# digital_input_module.net
KiCad netlist of a schematic drawn in Altium Designer
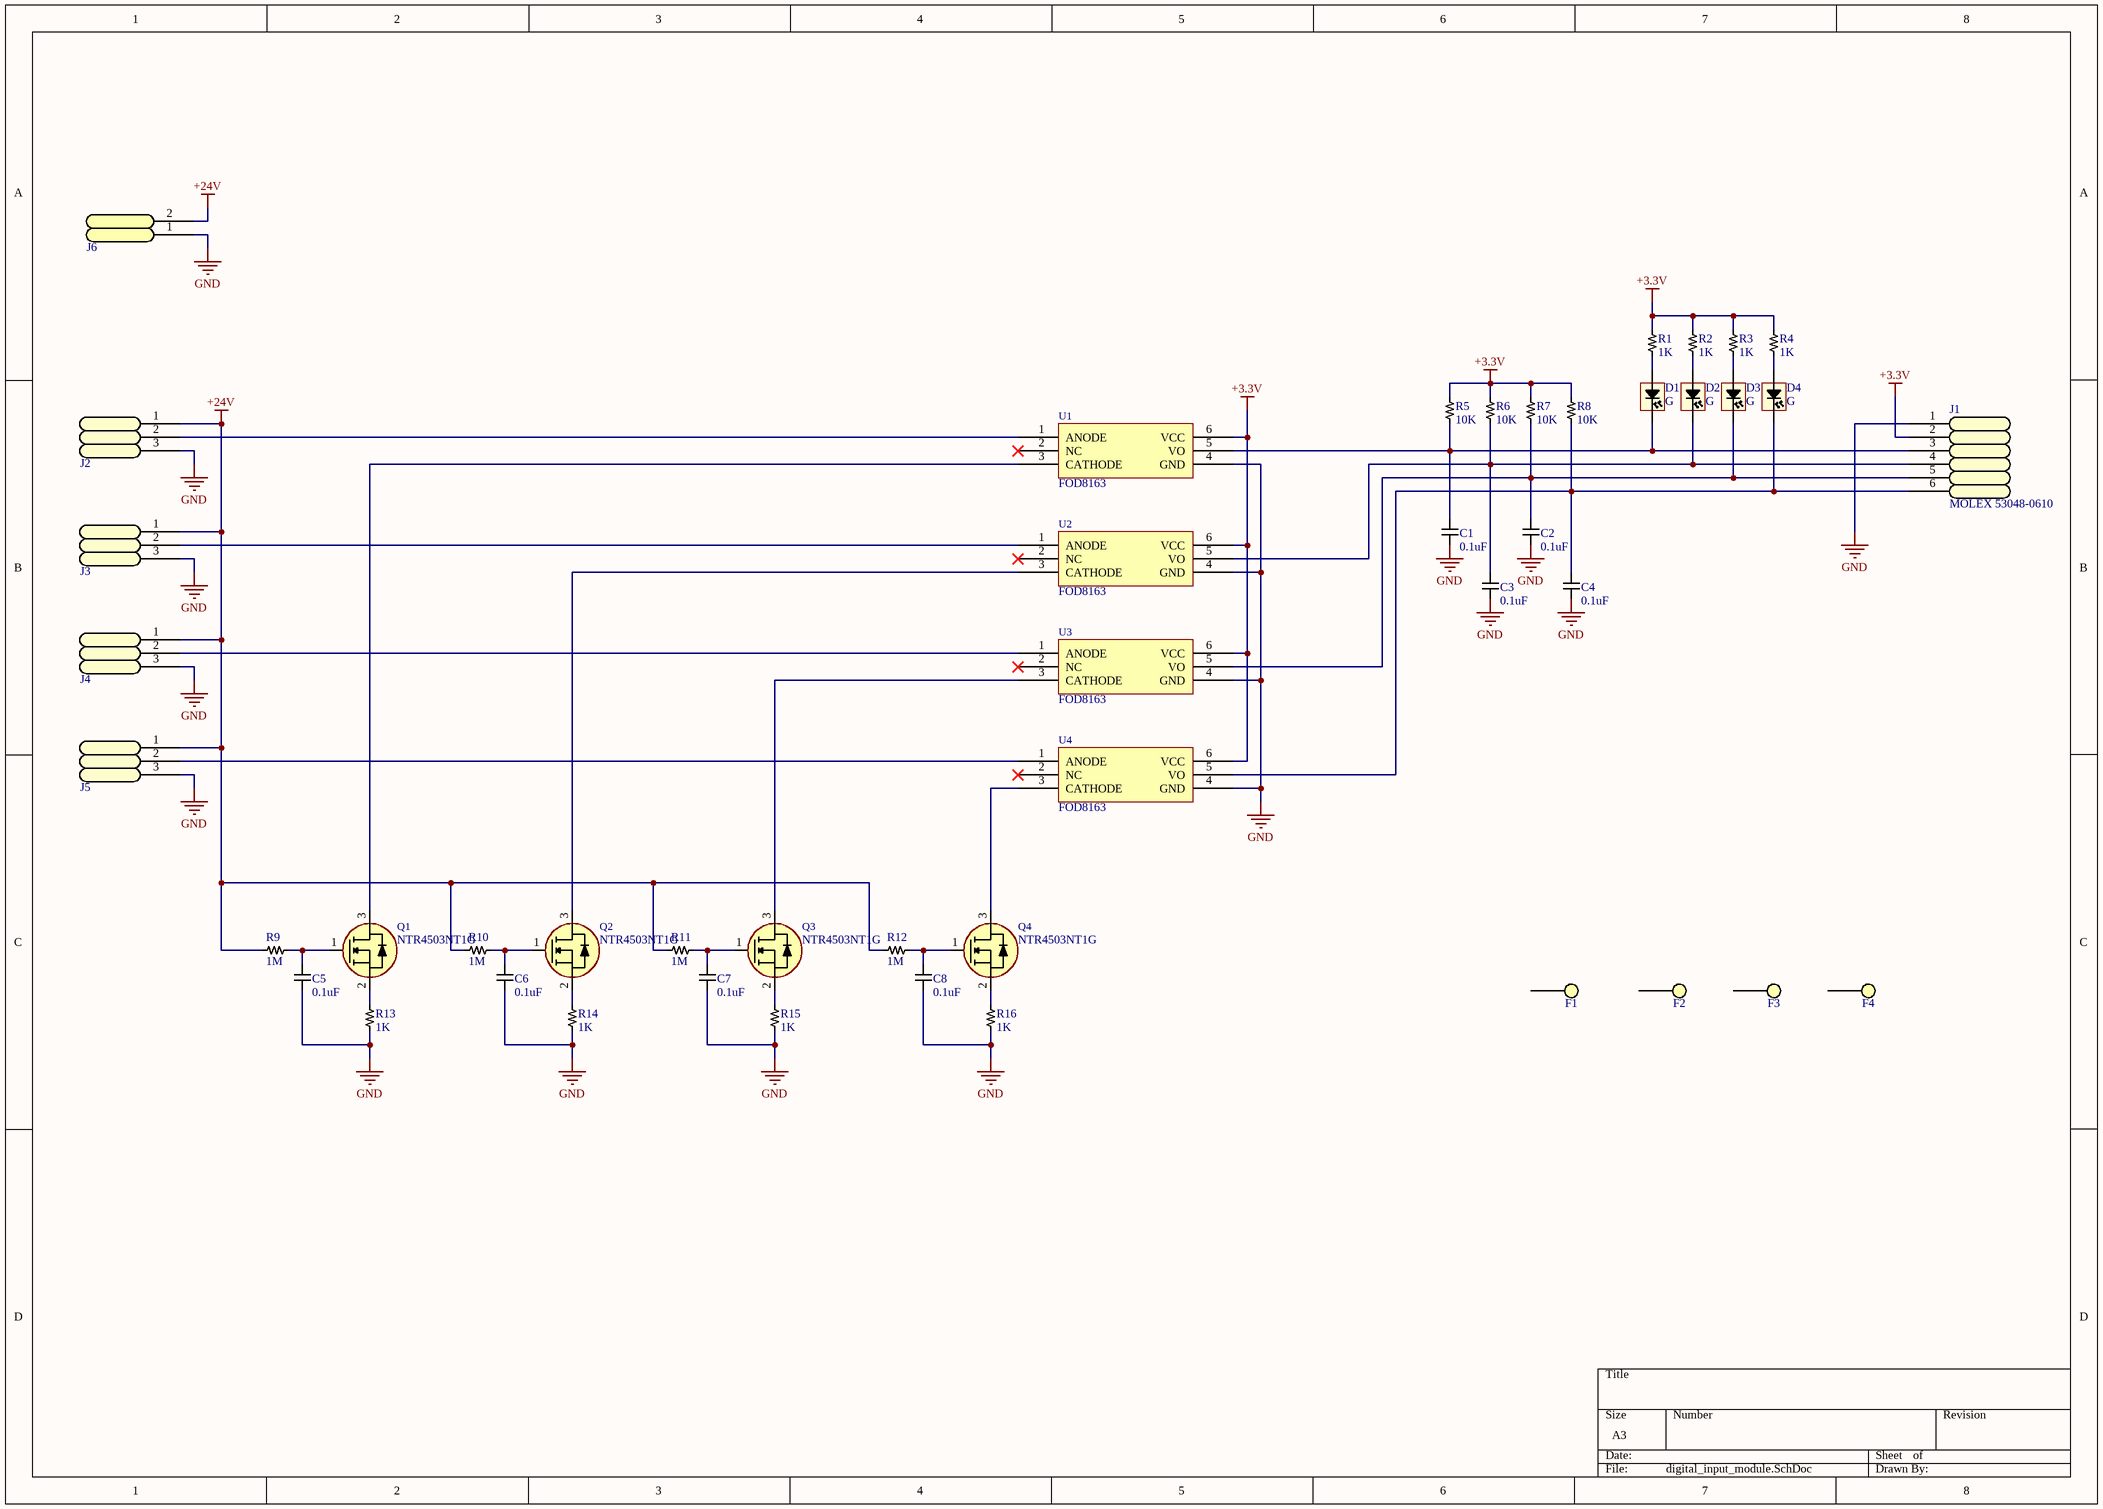
[diagram p0: digital_input_module.SchDoc]

(export (version "E")
  (design (tool "Eeschema 10.0.6"))
  (components
    (comp (ref "C1")
      (value "0.1uF")
      (footprint "CAP1608L")
      (description "Non-polarized Capacitor")
      (fields (field (name "Comment") "C"))
      (libsource (lib "digital_input_module") (part "C"))
    )
    (comp (ref "C2")
      (value "0.1uF")
      (footprint "CAP1608L")
      (description "Non-polarized Capacitor")
      (fields (field (name "Comment") "C"))
      (libsource (lib "digital_input_module") (part "C"))
    )
    (comp (ref "C3")
      (value "0.1uF")
      (footprint "CAP1608L")
      (description "Non-polarized Capacitor")
      (fields (field (name "Comment") "C"))
      (libsource (lib "digital_input_module") (part "C"))
    )
    (comp (ref "C4")
      (value "0.1uF")
      (footprint "CAP1608L")
      (description "Non-polarized Capacitor")
      (fields (field (name "Comment") "C"))
      (libsource (lib "digital_input_module") (part "C"))
    )
    (comp (ref "C5")
      (value "0.1uF")
      (footprint "CAP1608L")
      (description "Non-polarized Capacitor")
      (fields (field (name "Comment") "C"))
      (libsource (lib "digital_input_module") (part "C"))
    )
    (comp (ref "C6")
      (value "0.1uF")
      (footprint "CAP1608L")
      (description "Non-polarized Capacitor")
      (fields (field (name "Comment") "C"))
      (libsource (lib "digital_input_module") (part "C"))
    )
    (comp (ref "C7")
      (value "0.1uF")
      (footprint "CAP1608L")
      (description "Non-polarized Capacitor")
      (fields (field (name "Comment") "C"))
      (libsource (lib "digital_input_module") (part "C"))
    )
    (comp (ref "C8")
      (value "0.1uF")
      (footprint "CAP1608L")
      (description "Non-polarized Capacitor")
      (fields (field (name "Comment") "C"))
      (libsource (lib "digital_input_module") (part "C"))
    )
    (comp (ref "D1")
      (value "G")
      (footprint "LED1608L")
      (description "LED")
      (libsource (lib "digital_input_module") (part "LED"))
    )
    (comp (ref "D2")
      (value "G")
      (footprint "LED1608L")
      (description "LED")
      (libsource (lib "digital_input_module") (part "LED"))
    )
    (comp (ref "D3")
      (value "G")
      (footprint "LED1608L")
      (description "LED")
      (libsource (lib "digital_input_module") (part "LED"))
    )
    (comp (ref "D4")
      (value "G")
      (footprint "LED1608L")
      (description "LED")
      (libsource (lib "digital_input_module") (part "LED"))
    )
    (comp (ref "F1")
      (value "FIXED_HOLE")
      (footprint "FIXED_HOLE_PAD")
      (libsource (lib "digital_input_module") (part "FIXED_HOLE"))
    )
    (comp (ref "F2")
      (value "FIXED_HOLE")
      (footprint "FIXED_HOLE_PAD")
      (libsource (lib "digital_input_module") (part "FIXED_HOLE"))
    )
    (comp (ref "F3")
      (value "FIXED_HOLE")
      (footprint "FIXED_HOLE_PAD")
      (libsource (lib "digital_input_module") (part "FIXED_HOLE"))
    )
    (comp (ref "F4")
      (value "FIXED_HOLE")
      (footprint "FIXED_HOLE_PAD")
      (libsource (lib "digital_input_module") (part "FIXED_HOLE"))
    )
    (comp (ref "J1")
      (value "MOLEX 53048-0610")
      (footprint "MOLEX-53254-0670")
      (libsource (lib "digital_input_module") (part "MCON-6"))
    )
    (comp (ref "J2")
      (value "MCON-3")
      (footprint "MOLEX-53254-0370")
      (libsource (lib "digital_input_module") (part "MCON-3"))
    )
    (comp (ref "J3")
      (value "MCON-3")
      (footprint "MOLEX-53254-0370")
      (libsource (lib "digital_input_module") (part "MCON-3"))
    )
    (comp (ref "J4")
      (value "MCON-3")
      (footprint "MOLEX-53254-0370")
      (libsource (lib "digital_input_module") (part "MCON-3"))
    )
    (comp (ref "J5")
      (value "MCON-3")
      (footprint "MOLEX-53254-0370")
      (libsource (lib "digital_input_module") (part "MCON-3"))
    )
    (comp (ref "J6")
      (value "CON2")
      (footprint "DG128-5.0-02P")
      (description "Generic Connector 2 Pin")
      (libsource (lib "digital_input_module") (part "CON2"))
    )
    (comp (ref "Q1")
      (value "NTR4503NT1G")
      (footprint "SOT-23-3")
      (description "Power MOSFET,  30 V, 2.5 A, Single N−Channel, SOT−23")
      (fields (field (name "Comment") "NTR4503N"))
      (libsource (lib "digital_input_module") (part "NTR4503N"))
    )
    (comp (ref "Q2")
      (value "NTR4503NT1G")
      (footprint "SOT-23-3")
      (description "Power MOSFET,  30 V, 2.5 A, Single N−Channel, SOT−23")
      (fields (field (name "Comment") "NTR4503N"))
      (libsource (lib "digital_input_module") (part "NTR4503N"))
    )
    (comp (ref "Q3")
      (value "NTR4503NT1G")
      (footprint "SOT-23-3")
      (description "Power MOSFET,  30 V, 2.5 A, Single N−Channel, SOT−23")
      (fields (field (name "Comment") "NTR4503N"))
      (libsource (lib "digital_input_module") (part "NTR4503N"))
    )
    (comp (ref "Q4")
      (value "NTR4503NT1G")
      (footprint "SOT-23-3")
      (description "Power MOSFET,  30 V, 2.5 A, Single N−Channel, SOT−23")
      (fields (field (name "Comment") "NTR4503N"))
      (libsource (lib "digital_input_module") (part "NTR4503N"))
    )
    (comp (ref "R1")
      (value "1K")
      (footprint "RES1608L")
      (description "Resistor")
      (fields (field (name "Comment") "R"))
      (libsource (lib "digital_input_module") (part "R"))
    )
    (comp (ref "R2")
      (value "1K")
      (footprint "RES1608L")
      (description "Resistor")
      (fields (field (name "Comment") "R"))
      (libsource (lib "digital_input_module") (part "R"))
    )
    (comp (ref "R3")
      (value "1K")
      (footprint "RES1608L")
      (description "Resistor")
      (fields (field (name "Comment") "R"))
      (libsource (lib "digital_input_module") (part "R"))
    )
    (comp (ref "R4")
      (value "1K")
      (footprint "RES1608L")
      (description "Resistor")
      (fields (field (name "Comment") "R"))
      (libsource (lib "digital_input_module") (part "R"))
    )
    (comp (ref "R5")
      (value "10K")
      (footprint "RES1608L")
      (description "Resistor")
      (fields (field (name "Comment") "R"))
      (libsource (lib "digital_input_module") (part "R"))
    )
    (comp (ref "R6")
      (value "10K")
      (footprint "RES1608L")
      (description "Resistor")
      (fields (field (name "Comment") "R"))
      (libsource (lib "digital_input_module") (part "R"))
    )
    (comp (ref "R7")
      (value "10K")
      (footprint "RES1608L")
      (description "Resistor")
      (fields (field (name "Comment") "R"))
      (libsource (lib "digital_input_module") (part "R"))
    )
    (comp (ref "R8")
      (value "10K")
      (footprint "RES1608L")
      (description "Resistor")
      (fields (field (name "Comment") "R"))
      (libsource (lib "digital_input_module") (part "R"))
    )
    (comp (ref "R9")
      (value "1M")
      (footprint "RES1608L")
      (description "Resistor")
      (fields (field (name "Comment") "R"))
      (libsource (lib "digital_input_module") (part "R"))
    )
    (comp (ref "R10")
      (value "1M")
      (footprint "RES1608L")
      (description "Resistor")
      (fields (field (name "Comment") "R"))
      (libsource (lib "digital_input_module") (part "R"))
    )
    (comp (ref "R11")
      (value "1M")
      (footprint "RES1608L")
      (description "Resistor")
      (fields (field (name "Comment") "R"))
      (libsource (lib "digital_input_module") (part "R"))
    )
    (comp (ref "R12")
      (value "1M")
      (footprint "RES1608L")
      (description "Resistor")
      (fields (field (name "Comment") "R"))
      (libsource (lib "digital_input_module") (part "R"))
    )
    (comp (ref "R13")
      (value "1K")
      (footprint "RES1608L")
      (description "Resistor")
      (fields (field (name "Comment") "R"))
      (libsource (lib "digital_input_module") (part "R"))
    )
    (comp (ref "R14")
      (value "1K")
      (footprint "RES1608L")
      (description "Resistor")
      (fields (field (name "Comment") "R"))
      (libsource (lib "digital_input_module") (part "R"))
    )
    (comp (ref "R15")
      (value "1K")
      (footprint "RES1608L")
      (description "Resistor")
      (fields (field (name "Comment") "R"))
      (libsource (lib "digital_input_module") (part "R"))
    )
    (comp (ref "R16")
      (value "1K")
      (footprint "RES1608L")
      (description "Resistor")
      (fields (field (name "Comment") "R"))
      (libsource (lib "digital_input_module") (part "R"))
    )
    (comp (ref "U1")
      (value "FOD8163")
      (footprint "SOP-6W")
      (description "Logic Output Optocouplers 3.3V/5V Logic Gate Optocoupler")
      (libsource (lib "digital_input_module") (part "FOD8163"))
    )
    (comp (ref "U2")
      (value "FOD8163")
      (footprint "SOP-6W")
      (description "Logic Output Optocouplers 3.3V/5V Logic Gate Optocoupler")
      (libsource (lib "digital_input_module") (part "FOD8163"))
    )
    (comp (ref "U3")
      (value "FOD8163")
      (footprint "SOP-6W")
      (description "Logic Output Optocouplers 3.3V/5V Logic Gate Optocoupler")
      (libsource (lib "digital_input_module") (part "FOD8163"))
    )
    (comp (ref "U4")
      (value "FOD8163")
      (footprint "SOP-6W")
      (description "Logic Output Optocouplers 3.3V/5V Logic Gate Optocoupler")
      (libsource (lib "digital_input_module") (part "FOD8163"))
    )
  )
  (nets
    (net (code "1") (name "+3.3V") (class "Default")
      (node (ref "J1") (pin "2") (pinfunction "2_2") (pintype "passive"))
      (node (ref "R1") (pin "2") (pinfunction "2_2") (pintype "passive"))
      (node (ref "R2") (pin "2") (pinfunction "2_2") (pintype "passive"))
      (node (ref "R3") (pin "2") (pinfunction "2_2") (pintype "passive"))
      (node (ref "R4") (pin "2") (pinfunction "2_2") (pintype "passive"))
      (node (ref "R5") (pin "2") (pinfunction "2_2") (pintype "passive"))
      (node (ref "R6") (pin "2") (pinfunction "2_2") (pintype "passive"))
      (node (ref "R7") (pin "2") (pinfunction "2_2") (pintype "passive"))
      (node (ref "R8") (pin "2") (pinfunction "2_2") (pintype "passive"))
      (node (ref "U1") (pin "6") (pinfunction "VCC_6") (pintype "passive"))
      (node (ref "U2") (pin "6") (pinfunction "VCC_6") (pintype "passive"))
      (node (ref "U3") (pin "6") (pinfunction "VCC_6") (pintype "passive"))
      (node (ref "U4") (pin "6") (pinfunction "VCC_6") (pintype "passive"))
    )
    (net (code "2") (name "+24V") (class "Default")
      (node (ref "J2") (pin "1") (pinfunction "1_1") (pintype "passive"))
      (node (ref "J3") (pin "1") (pinfunction "1_1") (pintype "passive"))
      (node (ref "J4") (pin "1") (pinfunction "1_1") (pintype "passive"))
      (node (ref "J5") (pin "1") (pinfunction "1_1") (pintype "passive"))
      (node (ref "J6") (pin "2") (pinfunction "2_2") (pintype "passive"))
      (node (ref "R10") (pin "1") (pinfunction "1_1") (pintype "passive"))
      (node (ref "R11") (pin "1") (pinfunction "1_1") (pintype "passive"))
      (node (ref "R12") (pin "1") (pinfunction "1_1") (pintype "passive"))
      (node (ref "R9") (pin "1") (pinfunction "1_1") (pintype "passive"))
    )
    (net (code "3") (name "GND") (class "Default")
      (node (ref "C1") (pin "2") (pinfunction "2_2") (pintype "passive"))
      (node (ref "C2") (pin "2") (pinfunction "2_2") (pintype "passive"))
      (node (ref "C3") (pin "2") (pinfunction "2_2") (pintype "passive"))
      (node (ref "C4") (pin "2") (pinfunction "2_2") (pintype "passive"))
      (node (ref "C5") (pin "2") (pinfunction "2_2") (pintype "passive"))
      (node (ref "C6") (pin "2") (pinfunction "2_2") (pintype "passive"))
      (node (ref "C7") (pin "2") (pinfunction "2_2") (pintype "passive"))
      (node (ref "C8") (pin "2") (pinfunction "2_2") (pintype "passive"))
      (node (ref "J1") (pin "1") (pinfunction "1_1") (pintype "passive"))
      (node (ref "J2") (pin "3") (pinfunction "3_3") (pintype "passive"))
      (node (ref "J3") (pin "3") (pinfunction "3_3") (pintype "passive"))
      (node (ref "J4") (pin "3") (pinfunction "3_3") (pintype "passive"))
      (node (ref "J5") (pin "3") (pinfunction "3_3") (pintype "passive"))
      (node (ref "J6") (pin "1") (pinfunction "1_1") (pintype "passive"))
      (node (ref "R13") (pin "1") (pinfunction "1_1") (pintype "passive"))
      (node (ref "R14") (pin "1") (pinfunction "1_1") (pintype "passive"))
      (node (ref "R15") (pin "1") (pinfunction "1_1") (pintype "passive"))
      (node (ref "R16") (pin "1") (pinfunction "1_1") (pintype "passive"))
      (node (ref "U1") (pin "4") (pinfunction "GND_4") (pintype "passive"))
      (node (ref "U2") (pin "4") (pinfunction "GND_4") (pintype "passive"))
      (node (ref "U3") (pin "4") (pinfunction "GND_4") (pintype "passive"))
      (node (ref "U4") (pin "4") (pinfunction "GND_4") (pintype "passive"))
    )
    (net (code "4") (name "Net-(D1-Pad1)") (class "Default")
      (node (ref "D1") (pin "1") (pinfunction "1_1") (pintype "passive"))
      (node (ref "R1") (pin "1") (pinfunction "1_1") (pintype "passive"))
    )
    (net (code "5") (name "Net-(D2-Pad1)") (class "Default")
      (node (ref "D2") (pin "1") (pinfunction "1_1") (pintype "passive"))
      (node (ref "R2") (pin "1") (pinfunction "1_1") (pintype "passive"))
    )
    (net (code "6") (name "Net-(D3-Pad1)") (class "Default")
      (node (ref "D3") (pin "1") (pinfunction "1_1") (pintype "passive"))
      (node (ref "R3") (pin "1") (pinfunction "1_1") (pintype "passive"))
    )
    (net (code "7") (name "Net-(D4-Pad1)") (class "Default")
      (node (ref "D4") (pin "1") (pinfunction "1_1") (pintype "passive"))
      (node (ref "R4") (pin "1") (pinfunction "1_1") (pintype "passive"))
    )
    (net (code "8") (name "Net-(Q1-D)") (class "Default")
      (node (ref "Q1") (pin "3") (pinfunction "D_3") (pintype "passive"))
      (node (ref "U1") (pin "3") (pinfunction "CATHODE_3") (pintype "passive"))
    )
    (net (code "9") (name "Net-(Q1-G)") (class "Default")
      (node (ref "C5") (pin "1") (pinfunction "1_1") (pintype "passive"))
      (node (ref "Q1") (pin "1") (pinfunction "G_1") (pintype "passive"))
      (node (ref "R9") (pin "2") (pinfunction "2_2") (pintype "passive"))
    )
    (net (code "10") (name "Net-(Q1-S)") (class "Default")
      (node (ref "Q1") (pin "2") (pinfunction "S_2") (pintype "passive"))
      (node (ref "R13") (pin "2") (pinfunction "2_2") (pintype "passive"))
    )
    (net (code "11") (name "Net-(Q2-D)") (class "Default")
      (node (ref "Q2") (pin "3") (pinfunction "D_3") (pintype "passive"))
      (node (ref "U2") (pin "3") (pinfunction "CATHODE_3") (pintype "passive"))
    )
    (net (code "12") (name "Net-(Q2-G)") (class "Default")
      (node (ref "C6") (pin "1") (pinfunction "1_1") (pintype "passive"))
      (node (ref "Q2") (pin "1") (pinfunction "G_1") (pintype "passive"))
      (node (ref "R10") (pin "2") (pinfunction "2_2") (pintype "passive"))
    )
    (net (code "13") (name "Net-(Q2-S)") (class "Default")
      (node (ref "Q2") (pin "2") (pinfunction "S_2") (pintype "passive"))
      (node (ref "R14") (pin "2") (pinfunction "2_2") (pintype "passive"))
    )
    (net (code "14") (name "Net-(Q3-D)") (class "Default")
      (node (ref "Q3") (pin "3") (pinfunction "D_3") (pintype "passive"))
      (node (ref "U3") (pin "3") (pinfunction "CATHODE_3") (pintype "passive"))
    )
    (net (code "15") (name "Net-(Q3-G)") (class "Default")
      (node (ref "C7") (pin "1") (pinfunction "1_1") (pintype "passive"))
      (node (ref "Q3") (pin "1") (pinfunction "G_1") (pintype "passive"))
      (node (ref "R11") (pin "2") (pinfunction "2_2") (pintype "passive"))
    )
    (net (code "16") (name "Net-(Q3-S)") (class "Default")
      (node (ref "Q3") (pin "2") (pinfunction "S_2") (pintype "passive"))
      (node (ref "R15") (pin "2") (pinfunction "2_2") (pintype "passive"))
    )
    (net (code "17") (name "Net-(Q4-D)") (class "Default")
      (node (ref "Q4") (pin "3") (pinfunction "D_3") (pintype "passive"))
      (node (ref "U4") (pin "3") (pinfunction "CATHODE_3") (pintype "passive"))
    )
    (net (code "18") (name "Net-(Q4-G)") (class "Default")
      (node (ref "C8") (pin "1") (pinfunction "1_1") (pintype "passive"))
      (node (ref "Q4") (pin "1") (pinfunction "G_1") (pintype "passive"))
      (node (ref "R12") (pin "2") (pinfunction "2_2") (pintype "passive"))
    )
    (net (code "19") (name "Net-(Q4-S)") (class "Default")
      (node (ref "Q4") (pin "2") (pinfunction "S_2") (pintype "passive"))
      (node (ref "R16") (pin "2") (pinfunction "2_2") (pintype "passive"))
    )
    (net (code "20") (name "Net-(U1-ANODE)") (class "Default")
      (node (ref "J2") (pin "2") (pinfunction "2_2") (pintype "passive"))
      (node (ref "U1") (pin "1") (pinfunction "ANODE_1") (pintype "passive"))
    )
    (net (code "21") (name "Net-(U1-VO)") (class "Default")
      (node (ref "C1") (pin "1") (pinfunction "1_1") (pintype "passive"))
      (node (ref "D1") (pin "2") (pinfunction "2_2") (pintype "passive"))
      (node (ref "J1") (pin "3") (pinfunction "3_3") (pintype "passive"))
      (node (ref "R5") (pin "1") (pinfunction "1_1") (pintype "passive"))
      (node (ref "U1") (pin "5") (pinfunction "VO_5") (pintype "passive"))
    )
    (net (code "22") (name "Net-(U2-ANODE)") (class "Default")
      (node (ref "J3") (pin "2") (pinfunction "2_2") (pintype "passive"))
      (node (ref "U2") (pin "1") (pinfunction "ANODE_1") (pintype "passive"))
    )
    (net (code "23") (name "Net-(U2-VO)") (class "Default")
      (node (ref "C3") (pin "1") (pinfunction "1_1") (pintype "passive"))
      (node (ref "D2") (pin "2") (pinfunction "2_2") (pintype "passive"))
      (node (ref "J1") (pin "4") (pinfunction "4_4") (pintype "passive"))
      (node (ref "R6") (pin "1") (pinfunction "1_1") (pintype "passive"))
      (node (ref "U2") (pin "5") (pinfunction "VO_5") (pintype "passive"))
    )
    (net (code "24") (name "Net-(U3-ANODE)") (class "Default")
      (node (ref "J4") (pin "2") (pinfunction "2_2") (pintype "passive"))
      (node (ref "U3") (pin "1") (pinfunction "ANODE_1") (pintype "passive"))
    )
    (net (code "25") (name "Net-(U3-VO)") (class "Default")
      (node (ref "C2") (pin "1") (pinfunction "1_1") (pintype "passive"))
      (node (ref "D3") (pin "2") (pinfunction "2_2") (pintype "passive"))
      (node (ref "J1") (pin "5") (pinfunction "5_5") (pintype "passive"))
      (node (ref "R7") (pin "1") (pinfunction "1_1") (pintype "passive"))
      (node (ref "U3") (pin "5") (pinfunction "VO_5") (pintype "passive"))
    )
    (net (code "26") (name "Net-(U4-ANODE)") (class "Default")
      (node (ref "J5") (pin "2") (pinfunction "2_2") (pintype "passive"))
      (node (ref "U4") (pin "1") (pinfunction "ANODE_1") (pintype "passive"))
    )
    (net (code "27") (name "Net-(U4-VO)") (class "Default")
      (node (ref "C4") (pin "1") (pinfunction "1_1") (pintype "passive"))
      (node (ref "D4") (pin "2") (pinfunction "2_2") (pintype "passive"))
      (node (ref "J1") (pin "6") (pinfunction "6_6") (pintype "passive"))
      (node (ref "R8") (pin "1") (pinfunction "1_1") (pintype "passive"))
      (node (ref "U4") (pin "5") (pinfunction "VO_5") (pintype "passive"))
    )
    (net (code "28") (name "unconnected-(F1-Pad1)") (class "Default")
      (node (ref "F1") (pin "1") (pinfunction "1_1") (pintype "passive"))
    )
    (net (code "29") (name "unconnected-(F2-Pad1)") (class "Default")
      (node (ref "F2") (pin "1") (pinfunction "1_1") (pintype "passive"))
    )
    (net (code "30") (name "unconnected-(F3-Pad1)") (class "Default")
      (node (ref "F3") (pin "1") (pinfunction "1_1") (pintype "passive"))
    )
    (net (code "31") (name "unconnected-(F4-Pad1)") (class "Default")
      (node (ref "F4") (pin "1") (pinfunction "1_1") (pintype "passive"))
    )
    (net (code "32") (name "unconnected-(U1-NC-Pad2)") (class "Default")
      (node (ref "U1") (pin "2") (pinfunction "NC_2") (pintype "passive+no_connect"))
    )
    (net (code "33") (name "unconnected-(U2-NC-Pad2)") (class "Default")
      (node (ref "U2") (pin "2") (pinfunction "NC_2") (pintype "passive+no_connect"))
    )
    (net (code "34") (name "unconnected-(U3-NC-Pad2)") (class "Default")
      (node (ref "U3") (pin "2") (pinfunction "NC_2") (pintype "passive+no_connect"))
    )
    (net (code "35") (name "unconnected-(U4-NC-Pad2)") (class "Default")
      (node (ref "U4") (pin "2") (pinfunction "NC_2") (pintype "passive+no_connect"))
    )
  )
)
